# Copy_of_STM32_microcontroller_IOs.net
KiCad netlist of a schematic drawn in Altium Designer
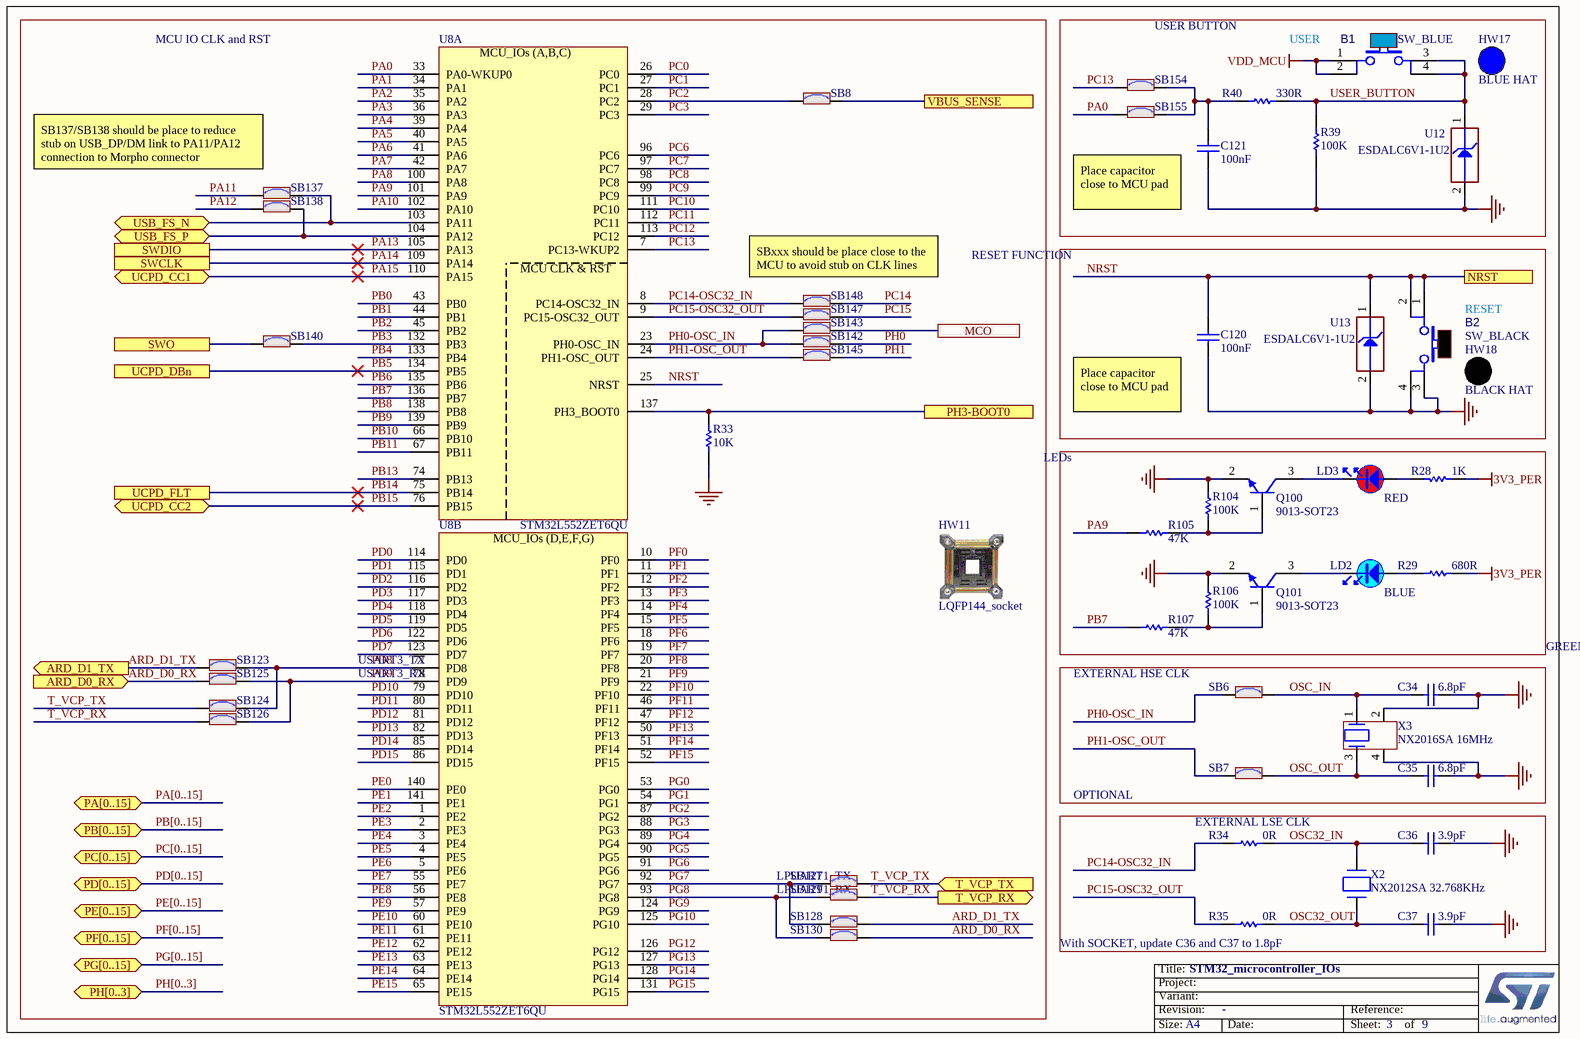
[diagram p0: Copy of STM32_microcontroller_IOs.SchDoc]

(export (version "E")
  (design (tool "Eeschema 10.0.6"))
  (components
    (comp (ref "B1")
      (value "SW_BLUE")
      (footprint "SWI_WEALTHMETAL_TD-0341_4P_BLUE")
      (description "Non-Open Push-Button 0.1A 24V BLUE")
      (fields
        (field (name "INTERNAL_PART_NUMBER") "MCD-00002")
        (field (name "MANUFACTURER_PART_NUMBER") "TD0341X-G01-BLU")
        (field (name "PROVIDED_BY") "Subcon")
      )
      (libsource (lib "MCD_PARTS_database") (part "SW-PUSH-CMS_BLUE"))
    )
    (comp (ref "B2")
      (value "SW_BLACK")
      (footprint "SWI_WEALTHMETAL_TD-0341_4P_BLACK")
      (description "Non-Open Push-Button 0.1A 24V BLACK")
      (fields
        (field (name "INTERNAL_PART_NUMBER") "MCD-00001")
        (field (name "MANUFACTURER_PART_NUMBER") "TD0341X-G01-BLA")
        (field (name "PROVIDED_BY") "Subcon")
      )
      (libsource (lib "MCD_PARTS_database") (part "SW-PUSH-CMS_BLACK"))
    )
    (comp (ref "C34")
      (value "6.8pF")
      (footprint "C0402")
      (description "Capacitor, MLCC, 6.8pF, 50V, NPO, +-0.25pF, 0402, T=0.5mm")
      (fields
        (field (name "INTERNAL_PART_NUMBER") "MCD-00674")
        (field (name "MANUFACTURER_PART_NUMBER") "CC0402CRNPO9BN6R8")
        (field (name "PROVIDED_BY") "Subcon")
      )
      (libsource (lib "MCD_PARTS_database") (part "Capacitor"))
    )
    (comp (ref "C35")
      (value "6.8pF")
      (footprint "C0402")
      (description "Capacitor, MLCC, 6.8pF, 50V, NPO, +-0.25pF, 0402, T=0.5mm")
      (fields
        (field (name "INTERNAL_PART_NUMBER") "MCD-00674")
        (field (name "MANUFACTURER_PART_NUMBER") "CC0402CRNPO9BN6R8")
        (field (name "PROVIDED_BY") "Subcon")
      )
      (libsource (lib "MCD_PARTS_database") (part "Capacitor"))
    )
    (comp (ref "C36")
      (value "3.9pF")
      (footprint "C0402")
      (description "Capacitor, MLCC, 3.9pF, 50V, NPO, +-0.25pF, 0402, T=0,5mm")
      (fields
        (field (name "INTERNAL_PART_NUMBER") "MCD-00556")
        (field (name "MANUFACTURER_PART_NUMBER") "CC0402CRNPO9BN3R9")
        (field (name "PROVIDED_BY") "SUBCO")
      )
      (libsource (lib "MCD_PARTS_database") (part "Capacitor"))
    )
    (comp (ref "C37")
      (value "3.9pF")
      (footprint "C0402")
      (description "Capacitor, MLCC, 3.9pF, 50V, NPO, +-0.25pF, 0402, T=0,5mm")
      (fields
        (field (name "INTERNAL_PART_NUMBER") "MCD-00556")
        (field (name "MANUFACTURER_PART_NUMBER") "CC0402CRNPO9BN3R9")
        (field (name "PROVIDED_BY") "SUBCO")
      )
      (libsource (lib "MCD_PARTS_database") (part "Capacitor"))
    )
    (comp (ref "C120")
      (value "100nF")
      (footprint "C0603")
      (description "Capacitor, MLCC, 100nF, 16V, X7R, 10%, 0603, T=0,8mm")
      (fields
        (field (name "INTERNAL_PART_NUMBER") "MCD-00211")
        (field (name "MANUFACTURER_PART_NUMBER") "CC0603KRX7R7BB104")
        (field (name "PROVIDED_BY") "Subcon")
      )
      (libsource (lib "MCD_PARTS_database") (part "Capacitor"))
    )
    (comp (ref "C121")
      (value "100nF")
      (footprint "C0603")
      (description "Capacitor, MLCC, 100nF, 16V, X7R, 10%, 0603, T=0,8mm")
      (fields
        (field (name "INTERNAL_PART_NUMBER") "MCD-00211")
        (field (name "MANUFACTURER_PART_NUMBER") "CC0603KRX7R7BB104")
        (field (name "PROVIDED_BY") "Subcon")
      )
      (libsource (lib "MCD_PARTS_database") (part "Capacitor"))
    )
    (comp (ref "HW11")
      (value "LQFP144_socket")
      (description "Yamaichi socket for LQFP144, with positioning pins.")
      (fields
        (field (name "INTERNAL_PART_NUMBER") "MCD-01015")
        (field (name "MANUFACTURER_PART_NUMBER") "IC149-144-145-B5")
        (field (name "PROVIDED_BY") "Subcon")
      )
      (libsource (lib "MCD_PARTS_database") (part "SOCKET_LQFP144"))
    )
    (comp (ref "HW17")
      (value "BLUE HAT")
      (description "Blue Hat for switch TD0341X-G01-BLU")
      (fields
        (field (name "INTERNAL_PART_NUMBER") "MCD-00634")
        (field (name "MANUFACTURER_PART_NUMBER") "988.16.09.3.00002_SH-517")
        (field (name "PROVIDED_BY") "Subcon")
      )
      (libsource (lib "MCD_PARTS_database") (part "BUTTON_HAT_BLUE"))
    )
    (comp (ref "HW18")
      (value "BLACK HAT")
      (description "Black Hat for switch TD0341X-G01-BLA")
      (fields
        (field (name "INTERNAL_PART_NUMBER") "MCD-00635")
        (field (name "MANUFACTURER_PART_NUMBER") "988.16.09.3.00003_SH-517")
        (field (name "PROVIDED_BY") "Subcon")
      )
      (libsource (lib "MCD_PARTS_database") (part "BUTTON_HAT_BLACK"))
    )
    (comp (ref "LD2")
      (value "BLUE")
      (footprint "LED_0603_VISHAY_VLMB1300-GS08_BLUE_1A2K_H0P8")
      (description "LED Blue, 0603 SMD, 3.3 V Forward Voltage")
      (fields
        (field (name "INTERNAL_PART_NUMBER") "MCD-00584")
        (field (name "MANUFACTURER_PART_NUMBER") "VLMB1300-GS08")
        (field (name "PROVIDED_BY") "Subcon")
      )
      (libsource (lib "MCD_PARTS_database") (part "LED_blue"))
    )
    (comp (ref "LD3")
      (value "RED")
      (footprint "LED_0603_RED_H0P4")
      (description "LED, Red, 0603")
      (fields
        (field (name "INTERNAL_PART_NUMBER") "MCD-00322")
        (field (name "MANUFACTURER_PART_NUMBER") "19-217/R6C-AL1M2VY/3T")
        (field (name "PROVIDED_BY") "Subcon")
      )
      (libsource (lib "MCD_PARTS_database") (part "LED_red"))
    )
    (comp (ref "Q100")
      (value "9013-SOT23")
      (footprint "NPN_SOT23")
      (description "NPN Bipolar Transistor")
      (fields
        (field (name "INTERNAL_PART_NUMBER") "MCD-00073")
        (field (name "MANUFACTURER_PART_NUMBER") "BSR14")
        (field (name "PROVIDED_BY") "Subcon")
      )
      (libsource (lib "MCD_PARTS_database") (part "9013-SOT23"))
    )
    (comp (ref "Q101")
      (value "9013-SOT23")
      (footprint "NPN_SOT23")
      (description "NPN Bipolar Transistor")
      (fields
        (field (name "INTERNAL_PART_NUMBER") "MCD-00073")
        (field (name "MANUFACTURER_PART_NUMBER") "BSR14")
        (field (name "PROVIDED_BY") "Subcon")
      )
      (libsource (lib "MCD_PARTS_database") (part "9013-SOT23"))
    )
    (comp (ref "R28")
      (value "1K")
      (footprint "R0603")
      (description "Resistor,1K,0603,1%,1/10W")
      (fields
        (field (name "INTERNAL_PART_NUMBER") "MCD-00070")
        (field (name "MANUFACTURER_PART_NUMBER") "RC0603FR-071KL")
        (field (name "PROVIDED_BY") "Subcon")
      )
      (libsource (lib "MCD_PARTS_database") (part "Resistor"))
    )
    (comp (ref "R29")
      (value "680R")
      (footprint "R0603")
      (description "Resistor,680R,0603,1%,1/10W")
      (fields
        (field (name "INTERNAL_PART_NUMBER") "MCD-00508")
        (field (name "MANUFACTURER_PART_NUMBER") "RC0603FR-07680RL")
        (field (name "PROVIDED_BY") "Subcon")
      )
      (libsource (lib "MCD_PARTS_database") (part "Resistor"))
    )
    (comp (ref "R33")
      (value "10K")
      (footprint "R0603")
      (description "Resistor,10K,0603,1%,1/10W")
      (fields
        (field (name "INTERNAL_PART_NUMBER") "MCD-00220")
        (field (name "MANUFACTURER_PART_NUMBER") "RC0603FR-0710KL")
        (field (name "PROVIDED_BY") "Subcon")
      )
      (libsource (lib "MCD_PARTS_database") (part "Resistor"))
    )
    (comp (ref "R34")
      (value "0R")
      (footprint "R0603")
      (description "Resistor,0R,0603,5%,1/10W")
      (fields
        (field (name "INTERNAL_PART_NUMBER") "MCD-00056")
        (field (name "MANUFACTURER_PART_NUMBER") "RC0603JR-070RL")
        (field (name "PROVIDED_BY") "subcon")
      )
      (libsource (lib "MCD_PARTS_database") (part "Resistor"))
    )
    (comp (ref "R35")
      (value "0R")
      (footprint "R0603")
      (description "Resistor,0R,0603,5%,1/10W")
      (fields
        (field (name "INTERNAL_PART_NUMBER") "MCD-00056")
        (field (name "MANUFACTURER_PART_NUMBER") "RC0603JR-070RL")
        (field (name "PROVIDED_BY") "subcon")
      )
      (libsource (lib "MCD_PARTS_database") (part "Resistor"))
    )
    (comp (ref "R39")
      (value "100K")
      (footprint "R0603")
      (description "Resistor,100K,0603,1%,1/10W")
      (fields
        (field (name "INTERNAL_PART_NUMBER") "MCD-00223")
        (field (name "MANUFACTURER_PART_NUMBER") "RC0603FR-07100KL")
        (field (name "PROVIDED_BY") "Subcon")
      )
      (libsource (lib "MCD_PARTS_database") (part "Resistor"))
    )
    (comp (ref "R40")
      (value "330R")
      (footprint "R0603")
      (description "Resistor,330R,0603,1%,1/10W")
      (fields
        (field (name "INTERNAL_PART_NUMBER") "MCD-00197")
        (field (name "MANUFACTURER_PART_NUMBER") "RC0603FR-07330RL")
        (field (name "PROVIDED_BY") "Subcon")
      )
      (libsource (lib "MCD_PARTS_database") (part "Resistor"))
    )
    (comp (ref "R104")
      (value "100K")
      (footprint "R0603")
      (description "Resistor,100K,0603,1%,1/10W")
      (fields
        (field (name "INTERNAL_PART_NUMBER") "MCD-00223")
        (field (name "MANUFACTURER_PART_NUMBER") "RC0603FR-07100KL")
        (field (name "PROVIDED_BY") "Subcon")
      )
      (libsource (lib "MCD_PARTS_database") (part "Resistor"))
    )
    (comp (ref "R105")
      (value "47K")
      (footprint "R0603")
      (description "Resistor,47K,0603,1%,1/10W")
      (fields
        (field (name "INTERNAL_PART_NUMBER") "MCD-00222")
        (field (name "MANUFACTURER_PART_NUMBER") "RC0603FR-0747KL")
        (field (name "PROVIDED_BY") "Subcon")
      )
      (libsource (lib "MCD_PARTS_database") (part "Resistor"))
    )
    (comp (ref "R106")
      (value "100K")
      (footprint "R0603")
      (description "Resistor,100K,0603,1%,1/10W")
      (fields
        (field (name "INTERNAL_PART_NUMBER") "MCD-00223")
        (field (name "MANUFACTURER_PART_NUMBER") "RC0603FR-07100KL")
        (field (name "PROVIDED_BY") "Subcon")
      )
      (libsource (lib "MCD_PARTS_database") (part "Resistor"))
    )
    (comp (ref "R107")
      (value "47K")
      (footprint "R0603")
      (description "Resistor,47K,0603,1%,1/10W")
      (fields
        (field (name "INTERNAL_PART_NUMBER") "MCD-00222")
        (field (name "MANUFACTURER_PART_NUMBER") "RC0603FR-0747KL")
        (field (name "PROVIDED_BY") "Subcon")
      )
      (libsource (lib "MCD_PARTS_database") (part "Resistor"))
    )
    (comp (ref "SB6")
      (value "~")
      (footprint "SOLDER-BRIDGE_R0603-0R")
      (description "Solder Bridge ON")
      (fields (field (name "INTERNAL_PART_NUMBER") "MCD-00071") (field (name "PROVIDED_BY") "Subcon"))
      (libsource (lib "") (part "SB_ON_1"))
    )
    (comp (ref "SB7")
      (value "~")
      (footprint "SOLDER-BRIDGE_R0603-0R")
      (description "Solder Bridge ON")
      (fields (field (name "INTERNAL_PART_NUMBER") "MCD-00071") (field (name "PROVIDED_BY") "Subcon"))
      (libsource (lib "") (part "SB_ON_1"))
    )
    (comp (ref "SB8")
      (value "~")
      (footprint "SOLDER-BRIDGE_R0603-0R")
      (description "Solder Bridge ON")
      (fields (field (name "INTERNAL_PART_NUMBER") "MCD-00071") (field (name "PROVIDED_BY") "Subcon"))
      (libsource (lib "") (part "SB_ON_1"))
    )
    (comp (ref "SB123")
      (value "~")
      (footprint "SOLDER-BRIDGE_R0603-0R")
      (description "Solder Bridge ON")
      (fields (field (name "INTERNAL_PART_NUMBER") "MCD-00071") (field (name "PROVIDED_BY") "Subcon"))
      (libsource (lib "MCD_PARTS_database") (part "SB_ON"))
    )
    (comp (ref "SB124")
      (value "~")
      (footprint "SOLDER-BRIDGE_R0603-0R")
      (description "Solder Bridge ON")
      (fields (field (name "INTERNAL_PART_NUMBER") "MCD-00071") (field (name "PROVIDED_BY") "Subcon"))
      (libsource (lib "MCD_PARTS_database") (part "SB_ON"))
    )
    (comp (ref "SB125")
      (value "~")
      (footprint "SOLDER-BRIDGE_R0603-0R")
      (description "Solder Bridge ON")
      (fields (field (name "INTERNAL_PART_NUMBER") "MCD-00071") (field (name "PROVIDED_BY") "Subcon"))
      (libsource (lib "MCD_PARTS_database") (part "SB_ON"))
    )
    (comp (ref "SB126")
      (value "~")
      (footprint "SOLDER-BRIDGE_R0603-0R")
      (description "Solder Bridge ON")
      (fields (field (name "INTERNAL_PART_NUMBER") "MCD-00071") (field (name "PROVIDED_BY") "Subcon"))
      (libsource (lib "MCD_PARTS_database") (part "SB_ON"))
    )
    (comp (ref "SB127")
      (value "~")
      (footprint "SOLDER-BRIDGE_R0603-0R")
      (description "Solder Bridge ON")
      (fields (field (name "INTERNAL_PART_NUMBER") "MCD-00071") (field (name "PROVIDED_BY") "Subcon"))
      (libsource (lib "MCD_PARTS_database") (part "SB_ON"))
    )
    (comp (ref "SB128")
      (value "~")
      (footprint "SOLDER-BRIDGE_R0603-0R")
      (description "Solder Bridge ON")
      (fields (field (name "INTERNAL_PART_NUMBER") "MCD-00071") (field (name "PROVIDED_BY") "Subcon"))
      (libsource (lib "MCD_PARTS_database") (part "SB_ON"))
    )
    (comp (ref "SB129")
      (value "~")
      (footprint "SOLDER-BRIDGE_R0603-0R")
      (description "Solder Bridge ON")
      (fields (field (name "INTERNAL_PART_NUMBER") "MCD-00071") (field (name "PROVIDED_BY") "Subcon"))
      (libsource (lib "MCD_PARTS_database") (part "SB_ON"))
    )
    (comp (ref "SB130")
      (value "~")
      (footprint "SOLDER-BRIDGE_R0603-0R")
      (description "Solder Bridge ON")
      (fields (field (name "INTERNAL_PART_NUMBER") "MCD-00071") (field (name "PROVIDED_BY") "Subcon"))
      (libsource (lib "MCD_PARTS_database") (part "SB_ON"))
    )
    (comp (ref "SB137")
      (value "~")
      (footprint "SOLDER-BRIDGE_R0603-0R")
      (description "Solder Bridge ON")
      (fields (field (name "INTERNAL_PART_NUMBER") "MCD-00071") (field (name "PROVIDED_BY") "Subcon"))
      (libsource (lib "") (part "SB_ON_1"))
    )
    (comp (ref "SB138")
      (value "~")
      (footprint "SOLDER-BRIDGE_R0603-0R")
      (description "Solder Bridge ON")
      (fields (field (name "INTERNAL_PART_NUMBER") "MCD-00071") (field (name "PROVIDED_BY") "Subcon"))
      (libsource (lib "") (part "SB_ON_1"))
    )
    (comp (ref "SB140")
      (value "~")
      (footprint "SOLDER-BRIDGE_R0603-0R")
      (description "Solder Bridge ON")
      (fields (field (name "INTERNAL_PART_NUMBER") "MCD-00071") (field (name "PROVIDED_BY") "Subcon"))
      (libsource (lib "") (part "SB_ON_1"))
    )
    (comp (ref "SB142")
      (value "~")
      (footprint "SOLDER-BRIDGE_R0603-0R")
      (description "Solder Bridge ON")
      (fields (field (name "INTERNAL_PART_NUMBER") "MCD-00071") (field (name "PROVIDED_BY") "Subcon"))
      (libsource (lib "") (part "SB_ON_1"))
    )
    (comp (ref "SB143")
      (value "~")
      (footprint "SOLDER-BRIDGE_R0603-0R")
      (description "Solder Bridge ON")
      (fields (field (name "INTERNAL_PART_NUMBER") "MCD-00071") (field (name "PROVIDED_BY") "Subcon"))
      (libsource (lib "") (part "SB_ON_1"))
    )
    (comp (ref "SB145")
      (value "~")
      (footprint "SOLDER-BRIDGE_R0603-0R")
      (description "Solder Bridge ON")
      (fields (field (name "INTERNAL_PART_NUMBER") "MCD-00071") (field (name "PROVIDED_BY") "Subcon"))
      (libsource (lib "") (part "SB_ON_1"))
    )
    (comp (ref "SB147")
      (value "~")
      (footprint "SOLDER-BRIDGE_R0603-0R")
      (description "Solder Bridge ON")
      (fields (field (name "INTERNAL_PART_NUMBER") "MCD-00071") (field (name "PROVIDED_BY") "Subcon"))
      (libsource (lib "") (part "SB_ON_1"))
    )
    (comp (ref "SB148")
      (value "~")
      (footprint "SOLDER-BRIDGE_R0603-0R")
      (description "Solder Bridge ON")
      (fields (field (name "INTERNAL_PART_NUMBER") "MCD-00071") (field (name "PROVIDED_BY") "Subcon"))
      (libsource (lib "") (part "SB_ON_1"))
    )
    (comp (ref "SB154")
      (value "~")
      (footprint "SOLDER-BRIDGE_R0603-0R")
      (description "Solder Bridge ON")
      (fields (field (name "INTERNAL_PART_NUMBER") "MCD-00071") (field (name "PROVIDED_BY") "Subcon"))
      (libsource (lib "MCD_PARTS_database") (part "SB_ON"))
    )
    (comp (ref "SB155")
      (value "~")
      (footprint "SOLDER-BRIDGE_R0603-0R")
      (description "Solder Bridge ON")
      (fields (field (name "INTERNAL_PART_NUMBER") "MCD-00071") (field (name "PROVIDED_BY") "Subcon"))
      (libsource (lib "MCD_PARTS_database") (part "SB_ON"))
    )
    (comp (ref "U8")
      (value "STM32L552ZET6QU")
      (footprint "ICC_LQFP144_20X20_P050")
      (description "STM32L552ZET6Q MCU,LQFP144 20x20, 0.5, no AES, Q for Int SMPS")
      (fields
        (field (name "INTERNAL_PART_NUMBER") "MCD-01055")
        (field (name "MANUFACTURER") "STMICROELECTRONICS")
        (field (name "PROVIDED_BY") "SUBCO with ST control")
      )
      (libsource (lib "MCD_PARTS_database") (part "STM32L552ZET6QU"))
    )
    (comp (ref "U12")
      (value "ESDALC6V1-1U2")
      (footprint "ESD_ST0201")
      (description "ESD protection 6V1")
      (fields
        (field (name "INTERNAL_PART_NUMBER") "MCD-00170")
        (field (name "MANUFACTURER") "STMICROELECTRONICS")
        (field (name "PROVIDED_BY") "Subcon")
      )
      (libsource (lib "MCD_PARTS_database") (part "ESD-TRANSIL"))
    )
    (comp (ref "U13")
      (value "ESDALC6V1-1U2")
      (footprint "ESD_ST0201")
      (description "ESD protection 6V1")
      (fields
        (field (name "INTERNAL_PART_NUMBER") "MCD-00170")
        (field (name "MANUFACTURER") "STMICROELECTRONICS")
        (field (name "PROVIDED_BY") "Subcon")
      )
      (libsource (lib "MCD_PARTS_database") (part "ESD-TRANSIL"))
    )
    (comp (ref "X2")
      (value "NX2012SA 32.768KHz")
      (footprint "CRY_NX2012SA_2P")
      (description "Crystal 32.768kHz, 6pF, -+20PPM, R=80K, SMD")
      (fields
        (field (name "INTERNAL_PART_NUMBER") "MCD-01479")
        (field (name "MANUFACTURER_PART_NUMBER") "NX2012SA 32.768KHz EXS00A-MU00527")
        (field (name "PROVIDED_BY") "SUBCO")
      )
      (libsource (lib "MCD_PARTS_database") (part "XTAL_2_PINS"))
    )
    (comp (ref "X3")
      (value "NX2016SA 16MHz")
      (footprint "CRY_NX2016SA_4P")
      (description "Crystal 16 MHz, 8pF, -+20 PPM, R=200Ω, SMD")
      (fields
        (field (name "INTERNAL_PART_NUMBER") "MCD-01476")
        (field (name "MANUFACTURER_PART_NUMBER") "NX2016SA 16 MHz EXS00A-CS07826")
      )
      (libsource (lib "MCD_PARTS_database") (part "XTAL_4_PINS"))
    )
  )
  (nets
    (net (code "7") (name "/ARD_D0_RX") (class "Default")
      (node (ref "SB125") (pin "2") (pinfunction "2_2") (pintype "passive"))
      (node (ref "SB130") (pin "1") (pinfunction "1_1") (pintype "passive"))
    )
    (net (code "8") (name "/ARD_D1_TX") (class "Default")
      (node (ref "SB123") (pin "2") (pinfunction "2_2") (pintype "passive"))
      (node (ref "SB128") (pin "1") (pinfunction "1_1") (pintype "passive"))
    )
    (net (code "9") (name "/MCO") (class "Default")
      (node (ref "SB143") (pin "2") (pinfunction "2_2") (pintype "passive"))
    )
    (net (code "10") (name "/NRST") (class "Default")
      (node (ref "B2") (pin "1") (pinfunction "1_1") (pintype "passive"))
      (node (ref "B2") (pin "2") (pinfunction "2_2") (pintype "passive"))
      (node (ref "C120") (pin "2") (pinfunction "2_2") (pintype "passive"))
      (node (ref "U13") (pin "1") (pinfunction "IO1_1") (pintype "passive"))
      (node (ref "U8") (pin "25") (pinfunction "NRST_25") (pintype "passive"))
    )
    (net (code "11") (name "/OSC32_IN") (class "Default")
      (node (ref "C36") (pin "1") (pinfunction "1_1") (pintype "passive"))
      (node (ref "R34") (pin "2") (pinfunction "2_2") (pintype "passive"))
      (node (ref "X2") (pin "2") (pinfunction "X2_2") (pintype "passive"))
    )
    (net (code "12") (name "/OSC32_OUT") (class "Default")
      (node (ref "C37") (pin "1") (pinfunction "1_1") (pintype "passive"))
      (node (ref "R35") (pin "2") (pinfunction "2_2") (pintype "passive"))
      (node (ref "X2") (pin "1") (pinfunction "X1_1") (pintype "passive"))
    )
    (net (code "13") (name "/OSC_IN") (class "Default")
      (node (ref "C34") (pin "1") (pinfunction "1_1") (pintype "passive"))
      (node (ref "SB6") (pin "2") (pinfunction "2_2") (pintype "passive"))
      (node (ref "X3") (pin "1") (pinfunction "1_1") (pintype "passive"))
    )
    (net (code "14") (name "/OSC_OUT") (class "Default")
      (node (ref "C35") (pin "1") (pinfunction "1_1") (pintype "passive"))
      (node (ref "SB7") (pin "2") (pinfunction "2_2") (pintype "passive"))
      (node (ref "X3") (pin "3") (pinfunction "3_3") (pintype "passive"))
    )
    (net (code "15") (name "/PA0") (class "Default")
      (node (ref "SB155") (pin "2") (pinfunction "2_2") (pintype "passive"))
      (node (ref "U8") (pin "33") (pinfunction "PA0-WKUP0_33") (pintype "passive"))
    )
    (net (code "16") (name "/PA1") (class "Default")
      (node (ref "U8") (pin "34") (pinfunction "PA1_34") (pintype "passive"))
    )
    (net (code "17") (name "/PA2") (class "Default")
      (node (ref "U8") (pin "35") (pinfunction "PA2_35") (pintype "passive"))
    )
    (net (code "18") (name "/PA3") (class "Default")
      (node (ref "U8") (pin "36") (pinfunction "PA3_36") (pintype "passive"))
    )
    (net (code "19") (name "/PA4") (class "Default")
      (node (ref "U8") (pin "39") (pinfunction "PA4_39") (pintype "passive"))
    )
    (net (code "20") (name "/PA5") (class "Default")
      (node (ref "U8") (pin "40") (pinfunction "PA5_40") (pintype "passive"))
    )
    (net (code "21") (name "/PA6") (class "Default")
      (node (ref "U8") (pin "41") (pinfunction "PA6_41") (pintype "passive"))
    )
    (net (code "22") (name "/PA7") (class "Default")
      (node (ref "U8") (pin "42") (pinfunction "PA7_42") (pintype "passive"))
    )
    (net (code "23") (name "/PA8") (class "Default")
      (node (ref "U8") (pin "100") (pinfunction "PA8_100") (pintype "passive"))
    )
    (net (code "24") (name "/PA9") (class "Default")
      (node (ref "R105") (pin "1") (pinfunction "1_1") (pintype "passive"))
      (node (ref "U8") (pin "101") (pinfunction "PA9_101") (pintype "passive"))
    )
    (net (code "25") (name "/PA10") (class "Default")
      (node (ref "U8") (pin "102") (pinfunction "PA10_102") (pintype "passive"))
    )
    (net (code "26") (name "/PA11") (class "Default")
      (node (ref "SB137") (pin "1") (pinfunction "1_1") (pintype "passive"))
    )
    (net (code "27") (name "/PA12") (class "Default")
      (node (ref "SB138") (pin "1") (pinfunction "1_1") (pintype "passive"))
    )
    (net (code "28") (name "/PA13") (class "Default")
      (node (ref "U8") (pin "105") (pinfunction "PA13_105") (pintype "passive"))
    )
    (net (code "29") (name "/PA14") (class "Default")
      (node (ref "U8") (pin "109") (pinfunction "PA14_109") (pintype "passive"))
    )
    (net (code "30") (name "/PA15") (class "Default")
      (node (ref "U8") (pin "110") (pinfunction "PA15_110") (pintype "passive"))
    )
    (net (code "32") (name "/PB0") (class "Default")
      (node (ref "U8") (pin "43") (pinfunction "PB0_43") (pintype "passive"))
    )
    (net (code "33") (name "/PB1") (class "Default")
      (node (ref "U8") (pin "44") (pinfunction "PB1_44") (pintype "passive"))
    )
    (net (code "34") (name "/PB2") (class "Default")
      (node (ref "U8") (pin "45") (pinfunction "PB2_45") (pintype "passive"))
    )
    (net (code "35") (name "/PB3") (class "Default")
      (node (ref "SB140") (pin "2") (pinfunction "2_2") (pintype "passive"))
      (node (ref "U8") (pin "132") (pinfunction "PB3_132") (pintype "passive"))
    )
    (net (code "36") (name "/PB4") (class "Default")
      (node (ref "U8") (pin "133") (pinfunction "PB4_133") (pintype "passive"))
    )
    (net (code "37") (name "/PB5") (class "Default")
      (node (ref "U8") (pin "134") (pinfunction "PB5_134") (pintype "passive"))
    )
    (net (code "38") (name "/PB6") (class "Default")
      (node (ref "U8") (pin "135") (pinfunction "PB6_135") (pintype "passive"))
    )
    (net (code "39") (name "/PB7") (class "Default")
      (node (ref "R107") (pin "1") (pinfunction "1_1") (pintype "passive"))
      (node (ref "U8") (pin "136") (pinfunction "PB7_136") (pintype "passive"))
    )
    (net (code "40") (name "/PB8") (class "Default")
      (node (ref "U8") (pin "138") (pinfunction "PB8_138") (pintype "passive"))
    )
    (net (code "41") (name "/PB9") (class "Default")
      (node (ref "U8") (pin "139") (pinfunction "PB9_139") (pintype "passive"))
    )
    (net (code "42") (name "/PB10") (class "Default")
      (node (ref "U8") (pin "66") (pinfunction "PB10_66") (pintype "passive"))
    )
    (net (code "43") (name "/PB11") (class "Default")
      (node (ref "U8") (pin "67") (pinfunction "PB11_67") (pintype "passive"))
    )
    (net (code "44") (name "/PB13") (class "Default")
      (node (ref "U8") (pin "74") (pinfunction "PB13_74") (pintype "passive"))
    )
    (net (code "45") (name "/PB14") (class "Default")
      (node (ref "U8") (pin "75") (pinfunction "PB14_75") (pintype "passive"))
    )
    (net (code "46") (name "/PB15") (class "Default")
      (node (ref "U8") (pin "76") (pinfunction "PB15_76") (pintype "passive"))
    )
    (net (code "48") (name "/PC0") (class "Default")
      (node (ref "U8") (pin "26") (pinfunction "PC0_26") (pintype "passive"))
    )
    (net (code "49") (name "/PC1") (class "Default")
      (node (ref "U8") (pin "27") (pinfunction "PC1_27") (pintype "passive"))
    )
    (net (code "50") (name "/PC2") (class "Default")
      (node (ref "SB8") (pin "1") (pinfunction "1_1") (pintype "passive"))
      (node (ref "U8") (pin "28") (pinfunction "PC2_28") (pintype "passive"))
    )
    (net (code "51") (name "/PC3") (class "Default")
      (node (ref "U8") (pin "29") (pinfunction "PC3_29") (pintype "passive"))
    )
    (net (code "52") (name "/PC6") (class "Default")
      (node (ref "U8") (pin "96") (pinfunction "PC6_96") (pintype "passive"))
    )
    (net (code "53") (name "/PC7") (class "Default")
      (node (ref "U8") (pin "97") (pinfunction "PC7_97") (pintype "passive"))
    )
    (net (code "54") (name "/PC8") (class "Default")
      (node (ref "U8") (pin "98") (pinfunction "PC8_98") (pintype "passive"))
    )
    (net (code "55") (name "/PC9") (class "Default")
      (node (ref "U8") (pin "99") (pinfunction "PC9_99") (pintype "passive"))
    )
    (net (code "56") (name "/PC10") (class "Default")
      (node (ref "U8") (pin "111") (pinfunction "PC10_111") (pintype "passive"))
    )
    (net (code "57") (name "/PC11") (class "Default")
      (node (ref "U8") (pin "112") (pinfunction "PC11_112") (pintype "passive"))
    )
    (net (code "58") (name "/PC12") (class "Default")
      (node (ref "U8") (pin "113") (pinfunction "PC12_113") (pintype "passive"))
    )
    (net (code "59") (name "/PC13") (class "Default")
      (node (ref "SB154") (pin "2") (pinfunction "2_2") (pintype "passive"))
      (node (ref "U8") (pin "7") (pinfunction "PC13-WKUP2_7") (pintype "passive"))
    )
    (net (code "60") (name "/PC14") (class "Default")
      (node (ref "SB148") (pin "2") (pinfunction "2_2") (pintype "passive"))
    )
    (net (code "61") (name "/PC14-OSC32_IN") (class "Default")
      (node (ref "R34") (pin "1") (pinfunction "1_1") (pintype "passive"))
      (node (ref "SB148") (pin "1") (pinfunction "1_1") (pintype "passive"))
      (node (ref "U8") (pin "8") (pinfunction "PC14-OSC32_IN_8") (pintype "passive"))
    )
    (net (code "62") (name "/PC15") (class "Default")
      (node (ref "SB147") (pin "2") (pinfunction "2_2") (pintype "passive"))
    )
    (net (code "63") (name "/PC15-OSC32_OUT") (class "Default")
      (node (ref "R35") (pin "1") (pinfunction "1_1") (pintype "passive"))
      (node (ref "SB147") (pin "1") (pinfunction "1_1") (pintype "passive"))
      (node (ref "U8") (pin "9") (pinfunction "PC15-OSC32_OUT_9") (pintype "passive"))
    )
    (net (code "65") (name "/PD0") (class "Default")
      (node (ref "U8") (pin "114") (pinfunction "PD0_114") (pintype "passive"))
    )
    (net (code "66") (name "/PD1") (class "Default")
      (node (ref "U8") (pin "115") (pinfunction "PD1_115") (pintype "passive"))
    )
    (net (code "67") (name "/PD2") (class "Default")
      (node (ref "U8") (pin "116") (pinfunction "PD2_116") (pintype "passive"))
    )
    (net (code "68") (name "/PD3") (class "Default")
      (node (ref "U8") (pin "117") (pinfunction "PD3_117") (pintype "passive"))
    )
    (net (code "69") (name "/PD4") (class "Default")
      (node (ref "U8") (pin "118") (pinfunction "PD4_118") (pintype "passive"))
    )
    (net (code "70") (name "/PD5") (class "Default")
      (node (ref "U8") (pin "119") (pinfunction "PD5_119") (pintype "passive"))
    )
    (net (code "71") (name "/PD6") (class "Default")
      (node (ref "U8") (pin "122") (pinfunction "PD6_122") (pintype "passive"))
    )
    (net (code "72") (name "/PD7") (class "Default")
      (node (ref "U8") (pin "123") (pinfunction "PD7_123") (pintype "passive"))
    )
    (net (code "73") (name "/PD8") (class "Default")
      (node (ref "SB123") (pin "1") (pinfunction "1_1") (pintype "passive"))
      (node (ref "SB124") (pin "1") (pinfunction "1_1") (pintype "passive"))
      (node (ref "U8") (pin "77") (pinfunction "PD8_77") (pintype "passive"))
    )
    (net (code "74") (name "/PD9") (class "Default")
      (node (ref "SB125") (pin "1") (pinfunction "1_1") (pintype "passive"))
      (node (ref "SB126") (pin "1") (pinfunction "1_1") (pintype "passive"))
      (node (ref "U8") (pin "78") (pinfunction "PD9_78") (pintype "passive"))
    )
    (net (code "75") (name "/PD10") (class "Default")
      (node (ref "U8") (pin "79") (pinfunction "PD10_79") (pintype "passive"))
    )
    (net (code "76") (name "/PD11") (class "Default")
      (node (ref "U8") (pin "80") (pinfunction "PD11_80") (pintype "passive"))
    )
    (net (code "77") (name "/PD12") (class "Default")
      (node (ref "U8") (pin "81") (pinfunction "PD12_81") (pintype "passive"))
    )
    (net (code "78") (name "/PD13") (class "Default")
      (node (ref "U8") (pin "82") (pinfunction "PD13_82") (pintype "passive"))
    )
    (net (code "79") (name "/PD14") (class "Default")
      (node (ref "U8") (pin "85") (pinfunction "PD14_85") (pintype "passive"))
    )
    (net (code "80") (name "/PD15") (class "Default")
      (node (ref "U8") (pin "86") (pinfunction "PD15_86") (pintype "passive"))
    )
    (net (code "82") (name "/PE0") (class "Default")
      (node (ref "U8") (pin "140") (pinfunction "PE0_140") (pintype "passive"))
    )
    (net (code "83") (name "/PE1") (class "Default")
      (node (ref "U8") (pin "141") (pinfunction "PE1_141") (pintype "passive"))
    )
    (net (code "84") (name "/PE2") (class "Default")
      (node (ref "U8") (pin "1") (pinfunction "PE2_1") (pintype "passive"))
    )
    (net (code "85") (name "/PE3") (class "Default")
      (node (ref "U8") (pin "2") (pinfunction "PE3_2") (pintype "passive"))
    )
    (net (code "86") (name "/PE4") (class "Default")
      (node (ref "U8") (pin "3") (pinfunction "PE4_3") (pintype "passive"))
    )
    (net (code "87") (name "/PE5") (class "Default")
      (node (ref "U8") (pin "4") (pinfunction "PE5_4") (pintype "passive"))
    )
    (net (code "88") (name "/PE6") (class "Default")
      (node (ref "U8") (pin "5") (pinfunction "PE6_5") (pintype "passive"))
    )
    (net (code "89") (name "/PE7") (class "Default")
      (node (ref "U8") (pin "55") (pinfunction "PE7_55") (pintype "passive"))
    )
    (net (code "90") (name "/PE8") (class "Default")
      (node (ref "U8") (pin "56") (pinfunction "PE8_56") (pintype "passive"))
    )
    (net (code "91") (name "/PE9") (class "Default")
      (node (ref "U8") (pin "57") (pinfunction "PE9_57") (pintype "passive"))
    )
    (net (code "92") (name "/PE10") (class "Default")
      (node (ref "U8") (pin "60") (pinfunction "PE10_60") (pintype "passive"))
    )
    (net (code "93") (name "/PE11") (class "Default")
      (node (ref "U8") (pin "61") (pinfunction "PE11_61") (pintype "passive"))
    )
    (net (code "94") (name "/PE12") (class "Default")
      (node (ref "U8") (pin "62") (pinfunction "PE12_62") (pintype "passive"))
    )
    (net (code "95") (name "/PE13") (class "Default")
      (node (ref "U8") (pin "63") (pinfunction "PE13_63") (pintype "passive"))
    )
    (net (code "96") (name "/PE14") (class "Default")
      (node (ref "U8") (pin "64") (pinfunction "PE14_64") (pintype "passive"))
    )
    (net (code "97") (name "/PE15") (class "Default")
      (node (ref "U8") (pin "65") (pinfunction "PE15_65") (pintype "passive"))
    )
    (net (code "99") (name "/PF0") (class "Default")
      (node (ref "U8") (pin "10") (pinfunction "PF0_10") (pintype "passive"))
    )
    (net (code "100") (name "/PF1") (class "Default")
      (node (ref "U8") (pin "11") (pinfunction "PF1_11") (pintype "passive"))
    )
    (net (code "101") (name "/PF2") (class "Default")
      (node (ref "U8") (pin "12") (pinfunction "PF2_12") (pintype "passive"))
    )
    (net (code "102") (name "/PF3") (class "Default")
      (node (ref "U8") (pin "13") (pinfunction "PF3_13") (pintype "passive"))
    )
    (net (code "103") (name "/PF4") (class "Default")
      (node (ref "U8") (pin "14") (pinfunction "PF4_14") (pintype "passive"))
    )
    (net (code "104") (name "/PF5") (class "Default")
      (node (ref "U8") (pin "15") (pinfunction "PF5_15") (pintype "passive"))
    )
    (net (code "105") (name "/PF6") (class "Default")
      (node (ref "U8") (pin "18") (pinfunction "PF6_18") (pintype "passive"))
    )
    (net (code "106") (name "/PF7") (class "Default")
      (node (ref "U8") (pin "19") (pinfunction "PF7_19") (pintype "passive"))
    )
    (net (code "107") (name "/PF8") (class "Default")
      (node (ref "U8") (pin "20") (pinfunction "PF8_20") (pintype "passive"))
    )
    (net (code "108") (name "/PF9") (class "Default")
      (node (ref "U8") (pin "21") (pinfunction "PF9_21") (pintype "passive"))
    )
    (net (code "109") (name "/PF10") (class "Default")
      (node (ref "U8") (pin "22") (pinfunction "PF10_22") (pintype "passive"))
    )
    (net (code "110") (name "/PF11") (class "Default")
      (node (ref "U8") (pin "46") (pinfunction "PF11_46") (pintype "passive"))
    )
    (net (code "111") (name "/PF12") (class "Default")
      (node (ref "U8") (pin "47") (pinfunction "PF12_47") (pintype "passive"))
    )
    (net (code "112") (name "/PF13") (class "Default")
      (node (ref "U8") (pin "50") (pinfunction "PF13_50") (pintype "passive"))
    )
    (net (code "113") (name "/PF14") (class "Default")
      (node (ref "U8") (pin "51") (pinfunction "PF14_51") (pintype "passive"))
    )
    (net (code "114") (name "/PF15") (class "Default")
      (node (ref "U8") (pin "52") (pinfunction "PF15_52") (pintype "passive"))
    )
    (net (code "116") (name "/PG0") (class "Default")
      (node (ref "U8") (pin "53") (pinfunction "PG0_53") (pintype "passive"))
    )
    (net (code "117") (name "/PG1") (class "Default")
      (node (ref "U8") (pin "54") (pinfunction "PG1_54") (pintype "passive"))
    )
    (net (code "118") (name "/PG2") (class "Default")
      (node (ref "U8") (pin "87") (pinfunction "PG2_87") (pintype "passive"))
    )
    (net (code "119") (name "/PG3") (class "Default")
      (node (ref "U8") (pin "88") (pinfunction "PG3_88") (pintype "passive"))
    )
    (net (code "120") (name "/PG4") (class "Default")
      (node (ref "U8") (pin "89") (pinfunction "PG4_89") (pintype "passive"))
    )
    (net (code "121") (name "/PG5") (class "Default")
      (node (ref "U8") (pin "90") (pinfunction "PG5_90") (pintype "passive"))
    )
    (net (code "122") (name "/PG6") (class "Default")
      (node (ref "U8") (pin "91") (pinfunction "PG6_91") (pintype "passive"))
    )
    (net (code "123") (name "/PG7") (class "Default")
      (node (ref "SB127") (pin "2") (pinfunction "2_2") (pintype "passive"))
      (node (ref "SB128") (pin "2") (pinfunction "2_2") (pintype "passive"))
      (node (ref "U8") (pin "92") (pinfunction "PG7_92") (pintype "passive"))
    )
    (net (code "124") (name "/PG8") (class "Default")
      (node (ref "SB129") (pin "2") (pinfunction "2_2") (pintype "passive"))
      (node (ref "SB130") (pin "2") (pinfunction "2_2") (pintype "passive"))
      (node (ref "U8") (pin "93") (pinfunction "PG8_93") (pintype "passive"))
    )
    (net (code "125") (name "/PG9") (class "Default")
      (node (ref "U8") (pin "124") (pinfunction "PG9_124") (pintype "passive"))
    )
    (net (code "126") (name "/PG10") (class "Default")
      (node (ref "U8") (pin "125") (pinfunction "PG10_125") (pintype "passive"))
    )
    (net (code "127") (name "/PG12") (class "Default")
      (node (ref "U8") (pin "126") (pinfunction "PG12_126") (pintype "passive"))
    )
    (net (code "128") (name "/PG13") (class "Default")
      (node (ref "U8") (pin "127") (pinfunction "PG13_127") (pintype "passive"))
    )
    (net (code "129") (name "/PG14") (class "Default")
      (node (ref "U8") (pin "128") (pinfunction "PG14_128") (pintype "passive"))
    )
    (net (code "130") (name "/PG15") (class "Default")
      (node (ref "U8") (pin "131") (pinfunction "PG15_131") (pintype "passive"))
    )
    (net (code "132") (name "/PH0") (class "Default")
      (node (ref "SB142") (pin "2") (pinfunction "2_2") (pintype "passive"))
    )
    (net (code "133") (name "/PH0-OSC_IN") (class "Default")
      (node (ref "SB142") (pin "1") (pinfunction "1_1") (pintype "passive"))
      (node (ref "SB143") (pin "1") (pinfunction "1_1") (pintype "passive"))
      (node (ref "SB6") (pin "1") (pinfunction "1_1") (pintype "passive"))
      (node (ref "U8") (pin "23") (pinfunction "PH0-OSC_IN_23") (pintype "passive"))
    )
    (net (code "134") (name "/PH1") (class "Default")
      (node (ref "SB145") (pin "2") (pinfunction "2_2") (pintype "passive"))
    )
    (net (code "135") (name "/PH1-OSC_OUT") (class "Default")
      (node (ref "SB145") (pin "1") (pinfunction "1_1") (pintype "passive"))
      (node (ref "SB7") (pin "1") (pinfunction "1_1") (pintype "passive"))
      (node (ref "U8") (pin "24") (pinfunction "PH1-OSC_OUT_24") (pintype "passive"))
    )
    (net (code "136") (name "/PH3-BOOT0") (class "Default")
      (node (ref "R33") (pin "1") (pinfunction "1_1") (pintype "passive"))
      (node (ref "U8") (pin "137") (pinfunction "PH3_BOOT0_137") (pintype "passive"))
    )
    (net (code "138") (name "/SWO") (class "Default")
      (node (ref "SB140") (pin "1") (pinfunction "1_1") (pintype "passive"))
    )
    (net (code "139") (name "/T_VCP_RX") (class "Default")
      (node (ref "SB126") (pin "2") (pinfunction "2_2") (pintype "passive"))
      (node (ref "SB129") (pin "1") (pinfunction "1_1") (pintype "passive"))
    )
    (net (code "140") (name "/T_VCP_TX") (class "Default")
      (node (ref "SB124") (pin "2") (pinfunction "2_2") (pintype "passive"))
      (node (ref "SB127") (pin "1") (pinfunction "1_1") (pintype "passive"))
    )
    (net (code "141") (name "/USB_FS_N") (class "Default")
      (node (ref "SB137") (pin "2") (pinfunction "2_2") (pintype "passive"))
      (node (ref "U8") (pin "103") (pinfunction "PA11_103") (pintype "passive"))
    )
    (net (code "142") (name "/USB_FS_P") (class "Default")
      (node (ref "SB138") (pin "2") (pinfunction "2_2") (pintype "passive"))
      (node (ref "U8") (pin "104") (pinfunction "PA12_104") (pintype "passive"))
    )
    (net (code "143") (name "/USER_BUTTON") (class "Default")
      (node (ref "B1") (pin "3") (pinfunction "3_3") (pintype "passive"))
      (node (ref "B1") (pin "4") (pinfunction "4_4") (pintype "passive"))
      (node (ref "R39") (pin "2") (pinfunction "2_2") (pintype "passive"))
      (node (ref "R40") (pin "2") (pinfunction "2_2") (pintype "passive"))
      (node (ref "U12") (pin "1") (pinfunction "IO1_1") (pintype "passive"))
    )
    (net (code "144") (name "/VBUS_SENSE") (class "Default")
      (node (ref "SB8") (pin "2") (pinfunction "2_2") (pintype "passive"))
    )
    (net (code "145") (name "3V3_PER") (class "Default")
      (node (ref "R28") (pin "1") (pinfunction "1_1") (pintype "passive"))
      (node (ref "R29") (pin "1") (pinfunction "1_1") (pintype "passive"))
    )
    (net (code "146") (name "GND") (class "Default")
      (node (ref "B2") (pin "3") (pinfunction "3_3") (pintype "passive"))
      (node (ref "B2") (pin "4") (pinfunction "4_4") (pintype "passive"))
      (node (ref "C120") (pin "1") (pinfunction "1_1") (pintype "passive"))
      (node (ref "C121") (pin "1") (pinfunction "1_1") (pintype "passive"))
      (node (ref "C34") (pin "2") (pinfunction "2_2") (pintype "passive"))
      (node (ref "C35") (pin "2") (pinfunction "2_2") (pintype "passive"))
      (node (ref "C36") (pin "2") (pinfunction "2_2") (pintype "passive"))
      (node (ref "C37") (pin "2") (pinfunction "2_2") (pintype "passive"))
      (node (ref "Q100") (pin "2") (pinfunction "E_2") (pintype "passive"))
      (node (ref "Q101") (pin "2") (pinfunction "E_2") (pintype "passive"))
      (node (ref "R104") (pin "1") (pinfunction "1_1") (pintype "passive"))
      (node (ref "R106") (pin "1") (pinfunction "1_1") (pintype "passive"))
      (node (ref "R33") (pin "2") (pinfunction "2_2") (pintype "passive"))
      (node (ref "R39") (pin "1") (pinfunction "1_1") (pintype "passive"))
      (node (ref "U12") (pin "2") (pinfunction "GND_2") (pintype "passive"))
      (node (ref "U13") (pin "2") (pinfunction "GND_2") (pintype "passive"))
      (node (ref "X3") (pin "2") (pinfunction "2_2") (pintype "passive"))
      (node (ref "X3") (pin "4") (pinfunction "4_4") (pintype "passive"))
    )
    (net (code "147") (name "Net-(C121-Pad2)") (class "Default")
      (node (ref "C121") (pin "2") (pinfunction "2_2") (pintype "passive"))
      (node (ref "R40") (pin "1") (pinfunction "1_1") (pintype "passive"))
      (node (ref "SB154") (pin "1") (pinfunction "1_1") (pintype "passive"))
      (node (ref "SB155") (pin "1") (pinfunction "1_1") (pintype "passive"))
    )
    (net (code "148") (name "Net-(LD2-Pad1)") (class "Default")
      (node (ref "LD2") (pin "1") (pintype "passive"))
      (node (ref "R29") (pin "2") (pinfunction "2_2") (pintype "passive"))
    )
    (net (code "149") (name "Net-(LD3-Pad1)") (class "Default")
      (node (ref "LD3") (pin "1") (pintype "passive"))
      (node (ref "R28") (pin "2") (pinfunction "2_2") (pintype "passive"))
    )
    (net (code "150") (name "Net-(Q100-B)") (class "Default")
      (node (ref "Q100") (pin "1") (pinfunction "B_1") (pintype "passive"))
      (node (ref "R104") (pin "2") (pinfunction "2_2") (pintype "passive"))
      (node (ref "R105") (pin "2") (pinfunction "2_2") (pintype "passive"))
    )
    (net (code "151") (name "Net-(Q100-C)") (class "Default")
      (node (ref "LD3") (pin "2") (pintype "passive"))
      (node (ref "Q100") (pin "3") (pinfunction "C_3") (pintype "passive"))
    )
    (net (code "152") (name "Net-(Q101-B)") (class "Default")
      (node (ref "Q101") (pin "1") (pinfunction "B_1") (pintype "passive"))
      (node (ref "R106") (pin "2") (pinfunction "2_2") (pintype "passive"))
      (node (ref "R107") (pin "2") (pinfunction "2_2") (pintype "passive"))
    )
    (net (code "153") (name "Net-(Q101-C)") (class "Default")
      (node (ref "LD2") (pin "2") (pintype "passive"))
      (node (ref "Q101") (pin "3") (pinfunction "C_3") (pintype "passive"))
    )
    (net (code "154") (name "VDD_MCU") (class "Default")
      (node (ref "B1") (pin "1") (pinfunction "1_1") (pintype "passive"))
      (node (ref "B1") (pin "2") (pinfunction "2_2") (pintype "passive"))
    )
  )
)
